# BT-RFID-Reader_v1_1.net
KiCad netlist of a schematic drawn in EAGLE
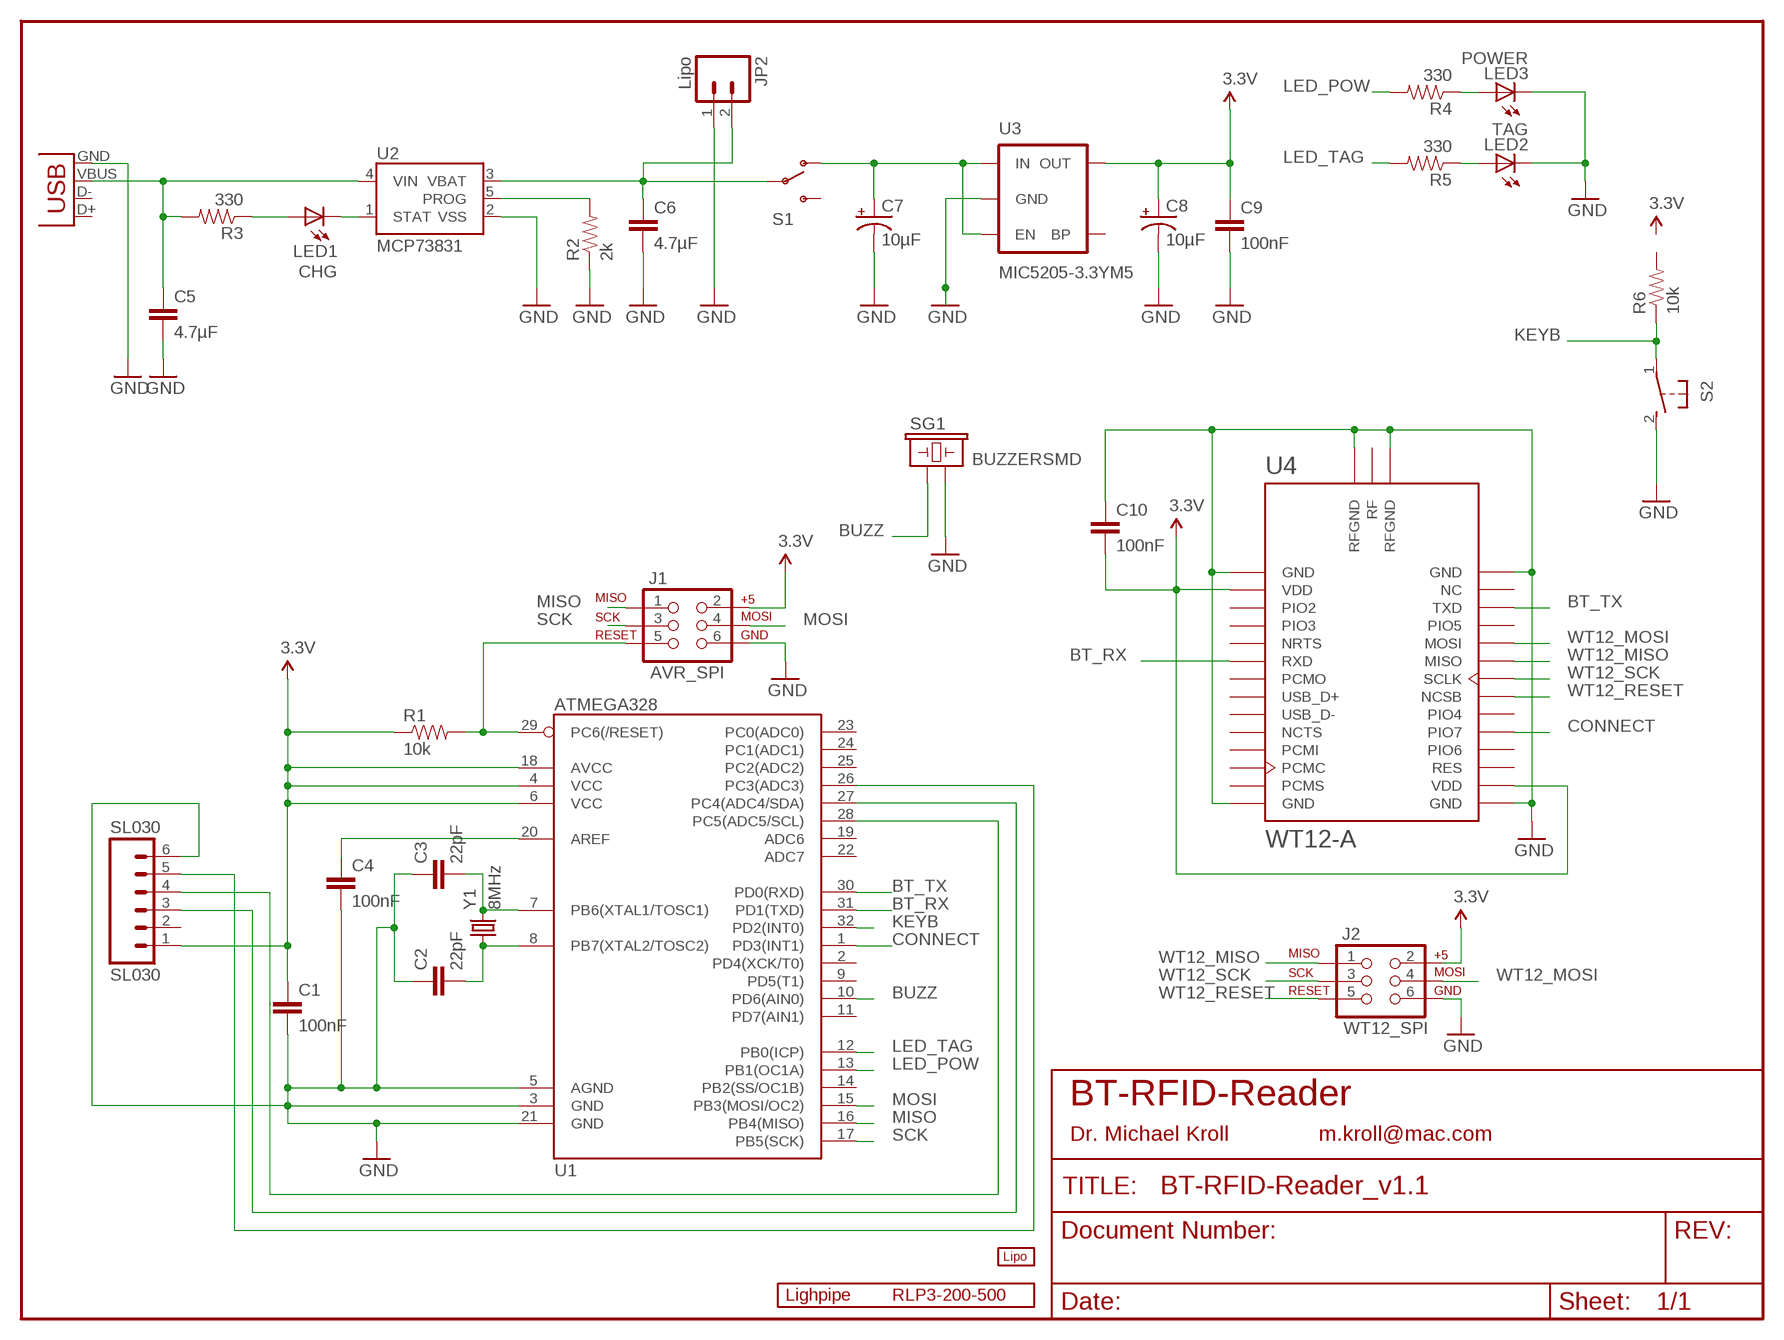
[diagram p0: schematic, sheet 1]

(export (version "E")
  (design (tool "Eeschema 10.0.6"))
  (components
    (comp (ref "C1")
      (value "100nF")
      (footprint "eagle-import:1206")
      (libsource (lib "eagle-import") (part "CAP1206"))
    )
    (comp (ref "C2")
      (value "22pF")
      (footprint "eagle-import:1206")
      (libsource (lib "eagle-import") (part "CAP1206"))
    )
    (comp (ref "C3")
      (value "22pF")
      (footprint "eagle-import:1206")
      (libsource (lib "eagle-import") (part "CAP1206"))
    )
    (comp (ref "C4")
      (value "100nF")
      (footprint "eagle-import:1206")
      (libsource (lib "eagle-import") (part "CAP1206"))
    )
    (comp (ref "C5")
      (value "4.7µF")
      (footprint "eagle-import:1206")
      (libsource (lib "eagle-import") (part "CAP1206"))
    )
    (comp (ref "C6")
      (value "4.7µF")
      (footprint "eagle-import:1206")
      (libsource (lib "eagle-import") (part "CAP1206"))
    )
    (comp (ref "C7")
      (value "10µF")
      (footprint "eagle-import:EIA3216")
      (libsource (lib "eagle-import") (part "CAP_POL1206"))
    )
    (comp (ref "C8")
      (value "10µF")
      (footprint "eagle-import:EIA3216")
      (libsource (lib "eagle-import") (part "CAP_POL1206"))
    )
    (comp (ref "C9")
      (value "100nF")
      (footprint "eagle-import:1206")
      (libsource (lib "eagle-import") (part "CAP1206"))
    )
    (comp (ref "C10")
      (value "100nF")
      (footprint "eagle-import:1206")
      (libsource (lib "eagle-import") (part "CAP1206"))
    )
    (comp (ref "J1")
      (value "AVR_SPI")
      (footprint "eagle-import:2X3")
      (libsource (lib "eagle-import") (part "AVR_SPI_PRG_6PTH"))
    )
    (comp (ref "J2")
      (value "WT12_SPI")
      (footprint "eagle-import:2X3")
      (libsource (lib "eagle-import") (part "AVR_SPI_PRG_6PTH"))
    )
    (comp (ref "JP2")
      (value "Lipo")
      (footprint "eagle-import:JST-2-SMD")
      (libsource (lib "eagle-import") (part "M02-JST-2MM-SMT"))
    )
    (comp (ref "LED1")
      (value "CHG")
      (footprint "eagle-import:LED-1206")
      (libsource (lib "eagle-import") (part "LED1206"))
    )
    (comp (ref "LED2")
      (value "TAG")
      (footprint "eagle-import:LED-1206-YELLOW")
      (libsource (lib "eagle-import") (part "LED1206-YELLOW"))
    )
    (comp (ref "LED3")
      (value "POWER")
      (footprint "eagle-import:LED-1206-GREEN")
      (libsource (lib "eagle-import") (part "LED1206-GREEN"))
    )
    (comp (ref "R1")
      (value "10k")
      (footprint "eagle-import:0805")
      (libsource (lib "eagle-import") (part "RESISTOR0805-RES"))
    )
    (comp (ref "R2")
      (value "2k")
      (footprint "eagle-import:0805")
      (libsource (lib "eagle-import") (part "RESISTOR0805-RES"))
    )
    (comp (ref "R3")
      (value "330")
      (footprint "eagle-import:0805")
      (libsource (lib "eagle-import") (part "RESISTOR0805-RES"))
    )
    (comp (ref "R4")
      (value "330")
      (footprint "eagle-import:0805")
      (libsource (lib "eagle-import") (part "RESISTOR0805-RES"))
    )
    (comp (ref "R5")
      (value "330")
      (footprint "eagle-import:0805")
      (libsource (lib "eagle-import") (part "RESISTOR0805-RES"))
    )
    (comp (ref "R6")
      (value "10k")
      (footprint "eagle-import:0805")
      (libsource (lib "eagle-import") (part "RESISTOR0805-RES"))
    )
    (comp (ref "S1")
      (value "SWITCH-SPSTSMD2")
      (footprint "eagle-import:SWITCH-SPDT-SMD")
      (libsource (lib "eagle-import") (part "SWITCH-SPSTSMD2"))
    )
    (comp (ref "S2")
      (value "31-XX")
      (footprint "eagle-import:B3F-31XX")
      (fields (field (name "MPN") "B3F-3100"))
      (libsource (lib "eagle-import") (part "31-XX"))
    )
    (comp (ref "SG1")
      (value "BUZZERSMD")
      (footprint "eagle-import:BUZZER-CMT1603")
      (libsource (lib "eagle-import") (part "BUZZERSMD"))
    )
    (comp (ref "SL030")
      (value "SL030")
      (footprint "eagle-import:SL030")
      (libsource (lib "eagle-import") (part "SL030"))
    )
    (comp (ref "U$1")
      (value "LIPO-OUTLINE1000")
      (footprint "eagle-import:LIPO-1000")
      (libsource (lib "eagle-import") (part "LIPO-OUTLINE1000"))
    )
    (comp (ref "U$2")
      (value "RLP3-200-500-OUTLINERLP3-200-500")
      (footprint "eagle-import:RLP3-200-500")
      (libsource (lib "eagle-import") (part "RLP3-200-500-OUTLINERLP3-200-500"))
    )
    (comp (ref "U1")
      (value "ATMEGA328")
      (footprint "eagle-import:TQFP32-08")
      (libsource (lib "eagle-import") (part "ATMEGA168"))
    )
    (comp (ref "U2")
      (value "MCP73831")
      (footprint "eagle-import:SOT23-5")
      (libsource (lib "eagle-import") (part "MCP73831"))
    )
    (comp (ref "U3")
      (value "MIC5205-3.3YM5")
      (footprint "eagle-import:SOT23-5")
      (libsource (lib "eagle-import") (part "V_REG_LDOSMD"))
    )
    (comp (ref "U4")
      (value "WT12-A")
      (footprint "eagle-import:WT12-A")
      (libsource (lib "eagle-import") (part "WT12-A-VISUAL"))
    )
    (comp (ref "X1")
      (value "USB-MICROB")
      (footprint "eagle-import:USB-MICROB")
      (libsource (lib "eagle-import") (part "USB-MICROB"))
    )
    (comp (ref "Y1")
      (value "8MHz")
      (footprint "eagle-import:HC49UP")
      (libsource (lib "eagle-import") (part "CRYSTALSMD"))
    )
  )
  (nets
    (net (code "1") (name "/BT_RX") (class "Default")
      (node (ref "U1") (pin "31") (pinfunction "PD1(TXD)_31") (pintype "bidirectional"))
      (node (ref "U4") (pin "RXD") (pinfunction "RXD_RXD") (pintype "input"))
    )
    (net (code "2") (name "/BT_TX") (class "Default")
      (node (ref "U1") (pin "30") (pinfunction "PD0(RXD)_30") (pintype "bidirectional"))
      (node (ref "U4") (pin "TXD") (pinfunction "TXD_TXD") (pintype "output"))
    )
    (net (code "3") (name "/BUZZ") (class "Default")
      (node (ref "SG1") (pin "P$1") (pinfunction "1_P$1") (pintype "passive"))
      (node (ref "U1") (pin "10") (pinfunction "PD6(AIN0)_10") (pintype "bidirectional"))
    )
    (net (code "4") (name "/CONNECT") (class "Default")
      (node (ref "U1") (pin "1") (pinfunction "PD3(INT1)_1") (pintype "bidirectional"))
      (node (ref "U4") (pin "PIO7") (pinfunction "PIO7_PIO7") (pintype "bidirectional"))
    )
    (net (code "5") (name "/KEYB") (class "Default")
      (node (ref "R6") (pin "1") (pinfunction "1_1") (pintype "passive"))
      (node (ref "S2") (pin "1") (pinfunction "P_1") (pintype "passive"))
      (node (ref "U1") (pin "32") (pinfunction "PD2(INT0)_32") (pintype "bidirectional"))
    )
    (net (code "6") (name "/LED_POW") (class "Default")
      (node (ref "R4") (pin "2") (pinfunction "2_2") (pintype "passive"))
      (node (ref "U1") (pin "13") (pinfunction "PB1(OC1A)_13") (pintype "bidirectional"))
    )
    (net (code "7") (name "/LED_TAG") (class "Default")
      (node (ref "R5") (pin "2") (pinfunction "2_2") (pintype "passive"))
      (node (ref "U1") (pin "12") (pinfunction "PB0(ICP)_12") (pintype "bidirectional"))
    )
    (net (code "8") (name "/MISO") (class "Default")
      (node (ref "J1") (pin "1") (pinfunction "1_1") (pintype "passive"))
      (node (ref "U1") (pin "16") (pinfunction "PB4(MISO)_16") (pintype "bidirectional"))
    )
    (net (code "9") (name "/MOSI") (class "Default")
      (node (ref "J1") (pin "4") (pinfunction "4_4") (pintype "passive"))
      (node (ref "U1") (pin "15") (pinfunction "PB3(MOSI/OC2)_15") (pintype "bidirectional"))
    )
    (net (code "10") (name "/SCK") (class "Default")
      (node (ref "J1") (pin "3") (pinfunction "3_3") (pintype "passive"))
      (node (ref "U1") (pin "17") (pinfunction "PB5(SCK)_17") (pintype "bidirectional"))
    )
    (net (code "11") (name "/WT12_MISO") (class "Default")
      (node (ref "J2") (pin "1") (pinfunction "1_1") (pintype "passive"))
      (node (ref "U4") (pin "MISO") (pinfunction "MISO_MISO") (pintype "output"))
    )
    (net (code "12") (name "/WT12_MOSI") (class "Default")
      (node (ref "J2") (pin "4") (pinfunction "4_4") (pintype "passive"))
      (node (ref "U4") (pin "MOSI") (pinfunction "MOSI_MOSI") (pintype "input"))
    )
    (net (code "13") (name "/WT12_RESET") (class "Default")
      (node (ref "J2") (pin "5") (pinfunction "5_5") (pintype "passive"))
      (node (ref "U4") (pin "NCSB") (pinfunction "NCSB_NCSB") (pintype "input"))
    )
    (net (code "14") (name "/WT12_SCK") (class "Default")
      (node (ref "J2") (pin "3") (pinfunction "3_3") (pintype "passive"))
      (node (ref "U4") (pin "SCLK") (pinfunction "SCLK_SCLK") (pintype "input"))
    )
    (net (code "15") (name "3.3V") (class "Default")
      (node (ref "C1") (pin "1") (pinfunction "1_1") (pintype "passive"))
      (node (ref "C10") (pin "2") (pinfunction "2_2") (pintype "passive"))
      (node (ref "C8") (pin "A") (pinfunction "+_A") (pintype "passive"))
      (node (ref "C9") (pin "1") (pinfunction "1_1") (pintype "passive"))
      (node (ref "J1") (pin "2") (pinfunction "2_2") (pintype "passive"))
      (node (ref "J2") (pin "2") (pinfunction "2_2") (pintype "passive"))
      (node (ref "R1") (pin "1") (pinfunction "1_1") (pintype "passive"))
      (node (ref "SL030") (pin "1") (pinfunction "VDD_1") (pintype "power_in"))
      (node (ref "U1") (pin "18") (pinfunction "AVCC_18") (pintype "bidirectional"))
      (node (ref "U1") (pin "4") (pinfunction "VCC_4") (pintype "bidirectional"))
      (node (ref "U1") (pin "6") (pinfunction "VCC_6") (pintype "bidirectional"))
      (node (ref "U3") (pin "5") (pinfunction "OUT_5") (pintype "passive"))
      (node (ref "U4") (pin "VDD1") (pinfunction "VDD_VDD1") (pintype "power_in"))
      (node (ref "U4") (pin "VDD2") (pinfunction "VDD_VDD2") (pintype "power_in"))
    )
    (net (code "16") (name "GND") (class "Default")
      (node (ref "C1") (pin "2") (pinfunction "2_2") (pintype "passive"))
      (node (ref "C10") (pin "1") (pinfunction "1_1") (pintype "passive"))
      (node (ref "C2") (pin "1") (pinfunction "1_1") (pintype "passive"))
      (node (ref "C3") (pin "1") (pinfunction "1_1") (pintype "passive"))
      (node (ref "C4") (pin "2") (pinfunction "2_2") (pintype "passive"))
      (node (ref "C5") (pin "2") (pinfunction "2_2") (pintype "passive"))
      (node (ref "C6") (pin "2") (pinfunction "2_2") (pintype "passive"))
      (node (ref "C7") (pin "C") (pinfunction "-_C") (pintype "passive"))
      (node (ref "C8") (pin "C") (pinfunction "-_C") (pintype "passive"))
      (node (ref "C9") (pin "2") (pinfunction "2_2") (pintype "passive"))
      (node (ref "J1") (pin "6") (pinfunction "6_6") (pintype "passive"))
      (node (ref "J2") (pin "6") (pinfunction "6_6") (pintype "passive"))
      (node (ref "JP2") (pin "1") (pinfunction "1_1") (pintype "passive"))
      (node (ref "LED2") (pin "C") (pinfunction "C_C") (pintype "passive"))
      (node (ref "LED3") (pin "C") (pinfunction "C_C") (pintype "passive"))
      (node (ref "R2") (pin "1") (pinfunction "1_1") (pintype "passive"))
      (node (ref "S2") (pin "2") (pinfunction "S_2") (pintype "passive"))
      (node (ref "SG1") (pin "P$2") (pinfunction "2_P$2") (pintype "passive"))
      (node (ref "SL030") (pin "6") (pinfunction "GND_6") (pintype "power_in"))
      (node (ref "U1") (pin "21") (pinfunction "GND_21") (pintype "bidirectional"))
      (node (ref "U1") (pin "3") (pinfunction "GND_3") (pintype "bidirectional"))
      (node (ref "U1") (pin "5") (pinfunction "AGND_5") (pintype "bidirectional"))
      (node (ref "U2") (pin "2") (pinfunction "VSS_2") (pintype "power_in"))
      (node (ref "U3") (pin "2") (pinfunction "GND_2") (pintype "input"))
      (node (ref "U4") (pin "GND1") (pinfunction "GND_GND1") (pintype "power_in"))
      (node (ref "U4") (pin "GND2") (pinfunction "GND_GND2") (pintype "power_in"))
      (node (ref "U4") (pin "GND3") (pinfunction "GND_GND3") (pintype "power_in"))
      (node (ref "U4") (pin "GND4") (pinfunction "GND_GND4") (pintype "power_in"))
      (node (ref "U4") (pin "RFGND1") (pinfunction "RFGND_RFGND1") (pintype "bidirectional"))
      (node (ref "U4") (pin "RFGND2") (pinfunction "RFGND_RFGND2") (pintype "bidirectional"))
      (node (ref "X1") (pin "GND") (pinfunction "GND_GND") (pintype "bidirectional"))
    )
    (net (code "17") (name "Net-(C7-+)") (class "Default")
      (node (ref "C7") (pin "A") (pinfunction "+_A") (pintype "passive"))
      (node (ref "S1") (pin "1") (pinfunction "O_1") (pintype "passive"))
      (node (ref "U3") (pin "1") (pinfunction "IN_1") (pintype "input"))
      (node (ref "U3") (pin "3") (pinfunction "EN_3") (pintype "input"))
    )
    (net (code "18") (name "Net-(LED1-PadA)") (class "Default")
      (node (ref "LED1") (pin "A") (pinfunction "A_A") (pintype "passive"))
      (node (ref "R3") (pin "1") (pinfunction "1_1") (pintype "passive"))
    )
    (net (code "19") (name "Net-(LED2-PadA)") (class "Default")
      (node (ref "LED2") (pin "A") (pinfunction "A_A") (pintype "passive"))
      (node (ref "R5") (pin "1") (pinfunction "1_1") (pintype "passive"))
    )
    (net (code "20") (name "Net-(LED3-PadA)") (class "Default")
      (node (ref "LED3") (pin "A") (pinfunction "A_A") (pintype "passive"))
      (node (ref "R4") (pin "1") (pinfunction "1_1") (pintype "passive"))
    )
    (net (code "21") (name "Net-(S1-P)") (class "Default")
      (node (ref "C6") (pin "1") (pinfunction "1_1") (pintype "passive"))
      (node (ref "JP2") (pin "2") (pinfunction "2_2") (pintype "passive"))
      (node (ref "S1") (pin "2") (pinfunction "P_2") (pintype "passive"))
      (node (ref "U2") (pin "3") (pinfunction "VBAT_3") (pintype "power_in"))
    )
    (net (code "22") (name "Net-(SL030-OUT)") (class "Default")
      (node (ref "SL030") (pin "5") (pinfunction "OUT_5") (pintype "output"))
      (node (ref "U1") (pin "26") (pinfunction "PC3(ADC3)_26") (pintype "bidirectional"))
    )
    (net (code "23") (name "Net-(SL030-SDA)") (class "Default")
      (node (ref "SL030") (pin "3") (pinfunction "SDA_3") (pintype "bidirectional"))
      (node (ref "U1") (pin "27") (pinfunction "PC4(ADC4/SDA)_27") (pintype "bidirectional"))
    )
    (net (code "24") (name "Net-(SL030-SLC)") (class "Default")
      (node (ref "SL030") (pin "4") (pinfunction "SLC_4") (pintype "input"))
      (node (ref "U1") (pin "28") (pinfunction "PC5(ADC5/SCL)_28") (pintype "bidirectional"))
    )
    (net (code "25") (name "Net-(U1-AREF)") (class "Default")
      (node (ref "C4") (pin "1") (pinfunction "1_1") (pintype "passive"))
      (node (ref "U1") (pin "20") (pinfunction "AREF_20") (pintype "bidirectional"))
    )
    (net (code "26") (name "Net-(U1-PB6(XTAL1{slash}TOSC1))") (class "Default")
      (node (ref "C3") (pin "2") (pinfunction "2_2") (pintype "passive"))
      (node (ref "U1") (pin "7") (pinfunction "PB6(XTAL1/TOSC1)_7") (pintype "bidirectional"))
      (node (ref "Y1") (pin "2") (pinfunction "2_2") (pintype "passive"))
    )
    (net (code "27") (name "Net-(U1-PB7(XTAL2{slash}TOSC2))") (class "Default")
      (node (ref "C2") (pin "2") (pinfunction "2_2") (pintype "passive"))
      (node (ref "U1") (pin "8") (pinfunction "PB7(XTAL2/TOSC2)_8") (pintype "bidirectional"))
      (node (ref "Y1") (pin "1") (pinfunction "1_1") (pintype "passive"))
    )
    (net (code "28") (name "Net-(U1-PC6({slash}RESET))") (class "Default")
      (node (ref "J1") (pin "5") (pinfunction "5_5") (pintype "passive"))
      (node (ref "R1") (pin "2") (pinfunction "2_2") (pintype "passive"))
      (node (ref "U1") (pin "29") (pinfunction "PC6(/RESET)_29") (pintype "bidirectional"))
    )
    (net (code "29") (name "Net-(U2-PROG)") (class "Default")
      (node (ref "R2") (pin "2") (pinfunction "2_2") (pintype "passive"))
      (node (ref "U2") (pin "5") (pinfunction "PROG_5") (pintype "input"))
    )
    (net (code "30") (name "Net-(U2-STAT)") (class "Default")
      (node (ref "LED1") (pin "C") (pinfunction "C_C") (pintype "passive"))
      (node (ref "U2") (pin "1") (pinfunction "STAT_1") (pintype "output"))
    )
    (net (code "31") (name "Net-(U2-VIN)") (class "Default")
      (node (ref "C5") (pin "1") (pinfunction "1_1") (pintype "passive"))
      (node (ref "R3") (pin "2") (pinfunction "2_2") (pintype "passive"))
      (node (ref "U2") (pin "4") (pinfunction "VIN_4") (pintype "power_in"))
      (node (ref "X1") (pin "VBUS") (pinfunction "VBUS_VBUS") (pintype "bidirectional"))
    )
    (net (code "32") (name "unconnected-(R6-Pad2)") (class "Default")
      (node (ref "R6") (pin "2") (pinfunction "2_2") (pintype "passive"))
    )
    (net (code "33") (name "unconnected-(S1-S-Pad3)") (class "Default")
      (node (ref "S1") (pin "3") (pinfunction "S_3") (pintype "passive"))
    )
    (net (code "34") (name "unconnected-(SL030-IN-Pad2)") (class "Default")
      (node (ref "SL030") (pin "2") (pinfunction "IN_2") (pintype "input"))
    )
    (net (code "35") (name "unconnected-(U1-ADC6-Pad19)") (class "Default")
      (node (ref "U1") (pin "19") (pinfunction "ADC6_19") (pintype "bidirectional"))
    )
    (net (code "36") (name "unconnected-(U1-ADC7-Pad22)") (class "Default")
      (node (ref "U1") (pin "22") (pinfunction "ADC7_22") (pintype "bidirectional"))
    )
    (net (code "37") (name "unconnected-(U1-PB2(SS{slash}OC1B)-Pad14)") (class "Default")
      (node (ref "U1") (pin "14") (pinfunction "PB2(SS/OC1B)_14") (pintype "bidirectional"))
    )
    (net (code "38") (name "unconnected-(U1-PC0(ADC0)-Pad23)") (class "Default")
      (node (ref "U1") (pin "23") (pinfunction "PC0(ADC0)_23") (pintype "bidirectional"))
    )
    (net (code "39") (name "unconnected-(U1-PC1(ADC1)-Pad24)") (class "Default")
      (node (ref "U1") (pin "24") (pinfunction "PC1(ADC1)_24") (pintype "bidirectional"))
    )
    (net (code "40") (name "unconnected-(U1-PC2(ADC2)-Pad25)") (class "Default")
      (node (ref "U1") (pin "25") (pinfunction "PC2(ADC2)_25") (pintype "bidirectional"))
    )
    (net (code "41") (name "unconnected-(U1-PD4(XCK{slash}T0)-Pad2)") (class "Default")
      (node (ref "U1") (pin "2") (pinfunction "PD4(XCK/T0)_2") (pintype "bidirectional"))
    )
    (net (code "42") (name "unconnected-(U1-PD5(T1)-Pad9)") (class "Default")
      (node (ref "U1") (pin "9") (pinfunction "PD5(T1)_9") (pintype "bidirectional"))
    )
    (net (code "43") (name "unconnected-(U1-PD7(AIN1)-Pad11)") (class "Default")
      (node (ref "U1") (pin "11") (pinfunction "PD7(AIN1)_11") (pintype "bidirectional"))
    )
    (net (code "44") (name "unconnected-(U3-BP-Pad4)") (class "Default")
      (node (ref "U3") (pin "4") (pinfunction "BP_4") (pintype "input"))
    )
    (net (code "45") (name "unconnected-(U4-PadNC)") (class "Default")
      (node (ref "U4") (pin "NC") (pinfunction "NC_NC") (pintype "no_connect"))
    )
    (net (code "46") (name "unconnected-(U4-PadNCTS)") (class "Default")
      (node (ref "U4") (pin "NCTS") (pinfunction "NCTS_NCTS") (pintype "input"))
    )
    (net (code "47") (name "unconnected-(U4-PadNRTS)") (class "Default")
      (node (ref "U4") (pin "NRTS") (pinfunction "NRTS_NRTS") (pintype "output"))
    )
    (net (code "48") (name "unconnected-(U4-PadPCMC)") (class "Default")
      (node (ref "U4") (pin "PCMC") (pinfunction "PCMC_PCMC") (pintype "bidirectional"))
    )
    (net (code "49") (name "unconnected-(U4-PadPCMI)") (class "Default")
      (node (ref "U4") (pin "PCMI") (pinfunction "PCMI_PCMI") (pintype "input"))
    )
    (net (code "50") (name "unconnected-(U4-PadPCMO)") (class "Default")
      (node (ref "U4") (pin "PCMO") (pinfunction "PCMO_PCMO") (pintype "output"))
    )
    (net (code "51") (name "unconnected-(U4-PadPCMS)") (class "Default")
      (node (ref "U4") (pin "PCMS") (pinfunction "PCMS_PCMS") (pintype "bidirectional"))
    )
    (net (code "52") (name "unconnected-(U4-PadPIO2)") (class "Default")
      (node (ref "U4") (pin "PIO2") (pinfunction "PIO2_PIO2") (pintype "bidirectional"))
    )
    (net (code "53") (name "unconnected-(U4-PadPIO3)") (class "Default")
      (node (ref "U4") (pin "PIO3") (pinfunction "PIO3_PIO3") (pintype "bidirectional"))
    )
    (net (code "54") (name "unconnected-(U4-PadPIO4)") (class "Default")
      (node (ref "U4") (pin "PIO4") (pinfunction "PIO4_PIO4") (pintype "bidirectional"))
    )
    (net (code "55") (name "unconnected-(U4-PadPIO5)") (class "Default")
      (node (ref "U4") (pin "PIO5") (pinfunction "PIO5_PIO5") (pintype "bidirectional"))
    )
    (net (code "56") (name "unconnected-(U4-PadPIO6)") (class "Default")
      (node (ref "U4") (pin "PIO6") (pinfunction "PIO6_PIO6") (pintype "bidirectional"))
    )
    (net (code "57") (name "unconnected-(U4-PadRES)") (class "Default")
      (node (ref "U4") (pin "RES") (pinfunction "RES_RES") (pintype "input"))
    )
    (net (code "58") (name "unconnected-(U4-PadRF)") (class "Default")
      (node (ref "U4") (pin "RF") (pinfunction "RF_RF") (pintype "bidirectional"))
    )
    (net (code "59") (name "unconnected-(U4-PadUSB_D+)") (class "Default")
      (node (ref "U4") (pin "USB_D+") (pinfunction "USB_D+_USB_D+") (pintype "bidirectional"))
    )
    (net (code "60") (name "unconnected-(U4-PadUSB_D-)") (class "Default")
      (node (ref "U4") (pin "USB_D-") (pinfunction "USB_D-_USB_D-") (pintype "bidirectional"))
    )
    (net (code "61") (name "unconnected-(X1-PadD+)") (class "Default")
      (node (ref "X1") (pin "D+") (pinfunction "D+_D+") (pintype "bidirectional"))
    )
    (net (code "62") (name "unconnected-(X1-PadD-)") (class "Default")
      (node (ref "X1") (pin "D-") (pinfunction "D-_D-") (pintype "bidirectional"))
    )
  )
)
